# Humidity_Temperature_Light.net
KiCad netlist of a schematic drawn in Altium Designer
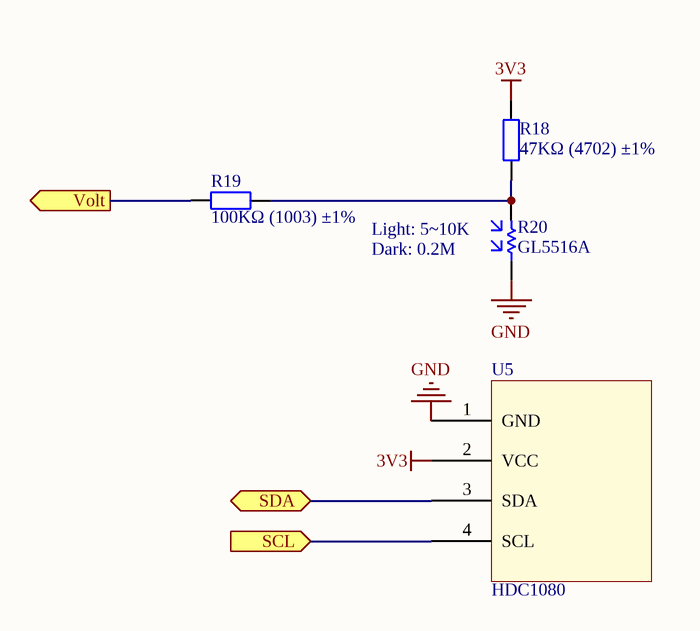
[diagram p0: Humidity&Temperature&Light.SchDoc]

(export (version "E")
  (design (tool "Eeschema 10.0.6"))
  (components
    (comp (ref "R18")
      (value "47KΩ (4702) ±1%")
      (footprint "0603_R")
      (description "贴片电阻")
      (libsource (lib "Miscellaneous Devices LC") (part "0603 47KΩ (4702) 1%"))
    )
    (comp (ref "R19")
      (value "100KΩ (1003) ±1%")
      (footprint "0603_R")
      (description "贴片电阻")
      (libsource (lib "Miscellaneous Devices LC") (part "0603 100KΩ (1003) 1%"))
    )
    (comp (ref "R20") (value "GL5516A") (footprint "GL5516A") (libsource (lib "lib") (part "GL5516A")))
    (comp (ref "U5") (value "HDC1080") (footprint "HDC1080") (libsource (lib "lib") (part "HDC1080")))
  )
  (nets
    (net (code "1") (name "/SCL") (class "Default")
      (node (ref "U5") (pin "4") (pinfunction "SCL_4") (pintype "passive"))
    )
    (net (code "2") (name "/SDA") (class "Default")
      (node (ref "U5") (pin "3") (pinfunction "SDA_3") (pintype "passive"))
    )
    (net (code "3") (name "/Volt") (class "Default")
      (node (ref "R19") (pin "1") (pinfunction "1_1") (pintype "passive"))
    )
    (net (code "4") (name "3V3") (class "Default")
      (node (ref "R18") (pin "2") (pinfunction "2_2") (pintype "passive"))
      (node (ref "U5") (pin "2") (pinfunction "VCC_2") (pintype "passive"))
    )
    (net (code "5") (name "GND") (class "Default")
      (node (ref "R20") (pin "1") (pinfunction "1_1") (pintype "passive"))
      (node (ref "U5") (pin "1") (pinfunction "GND_1") (pintype "passive"))
    )
    (net (code "6") (name "Net-(R18-Pad1)") (class "Default")
      (node (ref "R18") (pin "1") (pinfunction "1_1") (pintype "passive"))
      (node (ref "R19") (pin "2") (pinfunction "2_2") (pintype "passive"))
      (node (ref "R20") (pin "2") (pinfunction "2_2") (pintype "passive"))
    )
  )
)
